# RF.net
KiCad netlist of a schematic drawn in Altium Designer
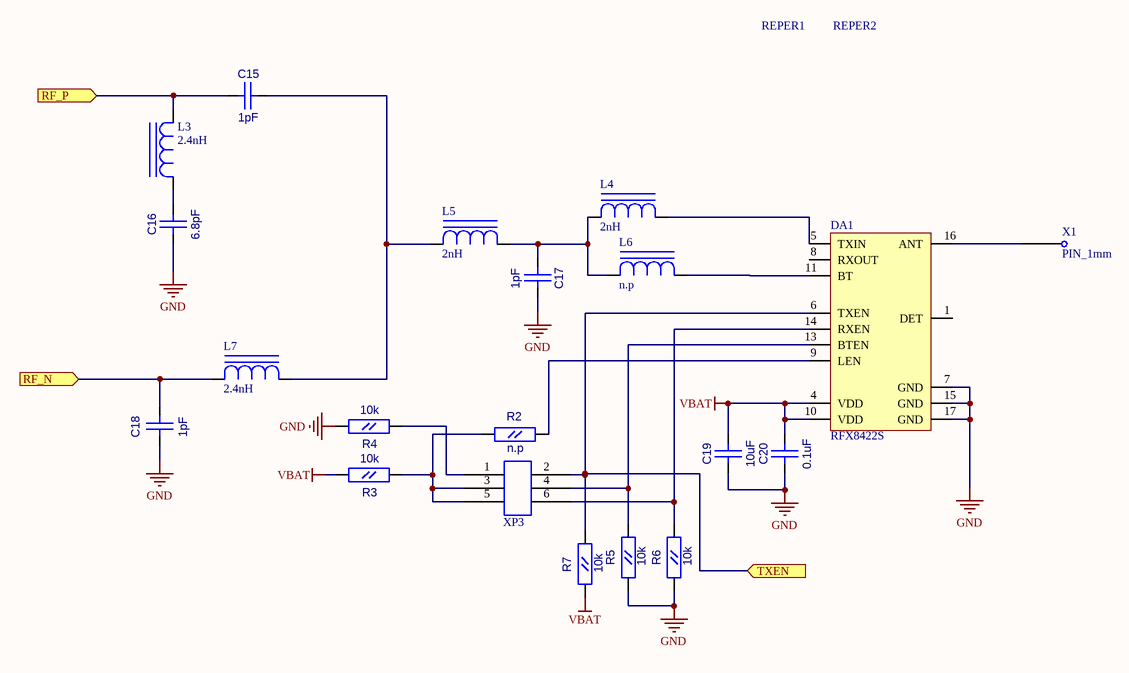
[diagram p0: RF.SchDoc]

(export (version "E")
  (design (tool "Eeschema 10.0.6"))
  (components
    (comp (ref "C15")
      (value "1pF")
      (footprint "CC0603")
      (description "CC0603")
      (libsource (lib "gprs_modem_2") (part "CC0603"))
    )
    (comp (ref "C16")
      (value "6.8pF")
      (footprint "CC0603")
      (description "CC0603")
      (libsource (lib "gprs_modem_2") (part "CC0603"))
    )
    (comp (ref "C17")
      (value "1pF")
      (footprint "CC0603")
      (description "CC0603")
      (libsource (lib "gprs_modem_2") (part "CC0603"))
    )
    (comp (ref "C18")
      (value "1pF")
      (footprint "CC0603")
      (description "CC0603")
      (libsource (lib "gprs_modem_2") (part "CC0603"))
    )
    (comp (ref "C19")
      (value "10uF")
      (footprint "CC0805")
      (description "CC0805")
      (libsource (lib "gprs_modem_2") (part "CC0805"))
    )
    (comp (ref "C20")
      (value "0.1uF")
      (footprint "CC0603")
      (description "CC0603")
      (libsource (lib "gprs_modem_2") (part "CC0603"))
    )
    (comp (ref "DA1")
      (value "RFX8422S")
      (footprint "QFN-16_Skyworks")
      (libsource (lib "gprs_modem_2") (part "RFX8422S"))
    )
    (comp (ref "L3")
      (value "2.4nH")
      (footprint "L0402")
      (description "L0402")
      (libsource (lib "gprs_modem_2") (part "L0402"))
    )
    (comp (ref "L4")
      (value "2nH")
      (footprint "L0402")
      (description "L0402")
      (libsource (lib "gprs_modem_2") (part "L0402"))
    )
    (comp (ref "L5")
      (value "2nH")
      (footprint "L0402")
      (description "L0402")
      (libsource (lib "gprs_modem_2") (part "L0402"))
    )
    (comp (ref "L6")
      (value "n.p")
      (footprint "L0402")
      (description "L0402")
      (libsource (lib "gprs_modem_2") (part "L0402"))
    )
    (comp (ref "L7")
      (value "2.4nH")
      (footprint "L0402")
      (description "L0402")
      (libsource (lib "gprs_modem_2") (part "L0402"))
    )
    (comp (ref "R2")
      (value "n.p")
      (footprint "RC0603")
      (description "RC0603")
      (libsource (lib "gprs_modem_2") (part "RC0603"))
    )
    (comp (ref "R3")
      (value "10k")
      (footprint "RC0603")
      (description "RC0603")
      (libsource (lib "gprs_modem_2") (part "RC0603"))
    )
    (comp (ref "R4")
      (value "10k")
      (footprint "RC0603")
      (description "RC0603")
      (libsource (lib "gprs_modem_2") (part "RC0603"))
    )
    (comp (ref "R5")
      (value "10k")
      (footprint "RC0603")
      (description "RC0603")
      (libsource (lib "gprs_modem_2") (part "RC0603"))
    )
    (comp (ref "R6")
      (value "10k")
      (footprint "RC0603")
      (description "RC0603")
      (libsource (lib "gprs_modem_2") (part "RC0603"))
    )
    (comp (ref "R7")
      (value "10k")
      (footprint "RC0603")
      (description "RC0603")
      (libsource (lib "gprs_modem_2") (part "RC0603"))
    )
    (comp (ref "REPER1")
      (value "REPER1.2")
      (footprint "REPER1.2")
      (libsource (lib "gprs_modem_2") (part "REPER1.2"))
    )
    (comp (ref "REPER2")
      (value "REPER1.2")
      (footprint "REPER1.2")
      (libsource (lib "gprs_modem_2") (part "REPER1.2"))
    )
    (comp (ref "X1")
      (value "PIN_1mm")
      (footprint "PIN_1mm")
      (libsource (lib "gprs_modem_2") (part "PIN_1mm"))
    )
    (comp (ref "XP3")
      (value "PLD06_SMD")
      (footprint "PLD06_SMD")
      (libsource (lib "gprs_modem_2") (part "PLD06_SMD"))
    )
  )
  (nets
    (net (code "1") (name "/RF_N") (class "Default")
      (node (ref "C18") (pin "1") (pinfunction "A_1") (pintype "passive"))
      (node (ref "L7") (pin "1") (pinfunction "A_1") (pintype "passive"))
    )
    (net (code "2") (name "/RF_P") (class "Default")
      (node (ref "C15") (pin "2") (pinfunction "B_2") (pintype "passive"))
      (node (ref "L3") (pin "2") (pinfunction "C_2") (pintype "passive"))
    )
    (net (code "3") (name "/TXEN") (class "Default")
      (node (ref "DA1") (pin "6") (pinfunction "TXEN_6") (pintype "passive"))
      (node (ref "R7") (pin "2") (pinfunction "B_2") (pintype "passive"))
      (node (ref "XP3") (pin "2") (pintype "passive"))
    )
    (net (code "4") (name "GND") (class "Default")
      (node (ref "C16") (pin "1") (pinfunction "A_1") (pintype "passive"))
      (node (ref "C17") (pin "2") (pinfunction "B_2") (pintype "passive"))
      (node (ref "C18") (pin "2") (pinfunction "B_2") (pintype "passive"))
      (node (ref "C19") (pin "1") (pinfunction "A_1") (pintype "passive"))
      (node (ref "C20") (pin "1") (pinfunction "A_1") (pintype "passive"))
      (node (ref "DA1") (pin "15") (pinfunction "GND_15") (pintype "passive"))
      (node (ref "DA1") (pin "17") (pinfunction "GND_17") (pintype "passive"))
      (node (ref "DA1") (pin "7") (pinfunction "GND_7") (pintype "passive"))
      (node (ref "R4") (pin "2") (pinfunction "B_2") (pintype "passive"))
      (node (ref "R5") (pin "1") (pinfunction "A_1") (pintype "passive"))
      (node (ref "R6") (pin "1") (pinfunction "A_1") (pintype "passive"))
    )
    (net (code "5") (name "Net-(C15-A)") (class "Default")
      (node (ref "C15") (pin "1") (pinfunction "A_1") (pintype "passive"))
      (node (ref "L5") (pin "1") (pinfunction "A_1") (pintype "passive"))
      (node (ref "L7") (pin "2") (pinfunction "C_2") (pintype "passive"))
    )
    (net (code "6") (name "Net-(C16-B)") (class "Default")
      (node (ref "C16") (pin "2") (pinfunction "B_2") (pintype "passive"))
      (node (ref "L3") (pin "1") (pinfunction "A_1") (pintype "passive"))
    )
    (net (code "7") (name "Net-(C17-A)") (class "Default")
      (node (ref "C17") (pin "1") (pinfunction "A_1") (pintype "passive"))
      (node (ref "L4") (pin "1") (pinfunction "A_1") (pintype "passive"))
      (node (ref "L5") (pin "2") (pinfunction "C_2") (pintype "passive"))
      (node (ref "L6") (pin "1") (pinfunction "A_1") (pintype "passive"))
    )
    (net (code "8") (name "Net-(DA1-ANT)") (class "Default")
      (node (ref "DA1") (pin "16") (pinfunction "ANT_16") (pintype "passive"))
      (node (ref "X1") (pin "1") (pinfunction "1_1") (pintype "passive"))
    )
    (net (code "9") (name "Net-(DA1-BT)") (class "Default")
      (node (ref "DA1") (pin "11") (pinfunction "BT_11") (pintype "passive"))
      (node (ref "L6") (pin "2") (pinfunction "C_2") (pintype "passive"))
    )
    (net (code "10") (name "Net-(DA1-BTEN)") (class "Default")
      (node (ref "DA1") (pin "13") (pinfunction "BTEN_13") (pintype "passive"))
      (node (ref "R5") (pin "2") (pinfunction "B_2") (pintype "passive"))
      (node (ref "XP3") (pin "4") (pintype "passive"))
    )
    (net (code "11") (name "Net-(DA1-LEN)") (class "Default")
      (node (ref "DA1") (pin "9") (pinfunction "LEN_9") (pintype "passive"))
      (node (ref "R2") (pin "2") (pinfunction "B_2") (pintype "passive"))
    )
    (net (code "12") (name "Net-(DA1-RXEN)") (class "Default")
      (node (ref "DA1") (pin "14") (pinfunction "RXEN_14") (pintype "passive"))
      (node (ref "R6") (pin "2") (pinfunction "B_2") (pintype "passive"))
      (node (ref "XP3") (pin "6") (pintype "passive"))
    )
    (net (code "13") (name "Net-(DA1-TXIN)") (class "Default")
      (node (ref "DA1") (pin "5") (pinfunction "TXIN_5") (pintype "passive"))
      (node (ref "L4") (pin "2") (pinfunction "C_2") (pintype "passive"))
    )
    (net (code "14") (name "Net-(R2-A)") (class "Default")
      (node (ref "R2") (pin "1") (pinfunction "A_1") (pintype "passive"))
      (node (ref "R3") (pin "1") (pinfunction "A_1") (pintype "passive"))
      (node (ref "XP3") (pin "3") (pintype "passive"))
      (node (ref "XP3") (pin "5") (pintype "passive"))
    )
    (net (code "15") (name "Net-(R4-A)") (class "Default")
      (node (ref "R4") (pin "1") (pinfunction "A_1") (pintype "passive"))
      (node (ref "XP3") (pin "1") (pintype "passive"))
    )
    (net (code "16") (name "VBAT") (class "Default")
      (node (ref "C19") (pin "2") (pinfunction "B_2") (pintype "passive"))
      (node (ref "C20") (pin "2") (pinfunction "B_2") (pintype "passive"))
      (node (ref "DA1") (pin "10") (pinfunction "VDD_10") (pintype "passive"))
      (node (ref "DA1") (pin "4") (pinfunction "VDD_4") (pintype "passive"))
      (node (ref "R3") (pin "2") (pinfunction "B_2") (pintype "passive"))
      (node (ref "R7") (pin "1") (pinfunction "A_1") (pintype "passive"))
    )
    (net (code "17") (name "unconnected-(DA1-DET-Pad1)") (class "Default")
      (node (ref "DA1") (pin "1") (pinfunction "DET_1") (pintype "passive"))
    )
    (net (code "18") (name "unconnected-(DA1-RXOUT-Pad8)") (class "Default")
      (node (ref "DA1") (pin "8") (pinfunction "RXOUT_8") (pintype "passive"))
    )
    (net (code "19") (name "unconnected-(REPER1-Pad1)") (class "Default")
      (node (ref "REPER1") (pin "1") (pintype "passive"))
    )
    (net (code "20") (name "unconnected-(REPER2-Pad1)") (class "Default")
      (node (ref "REPER2") (pin "1") (pintype "passive"))
    )
  )
)
